# Drivers.net
KiCad netlist of a schematic drawn in Altium Designer
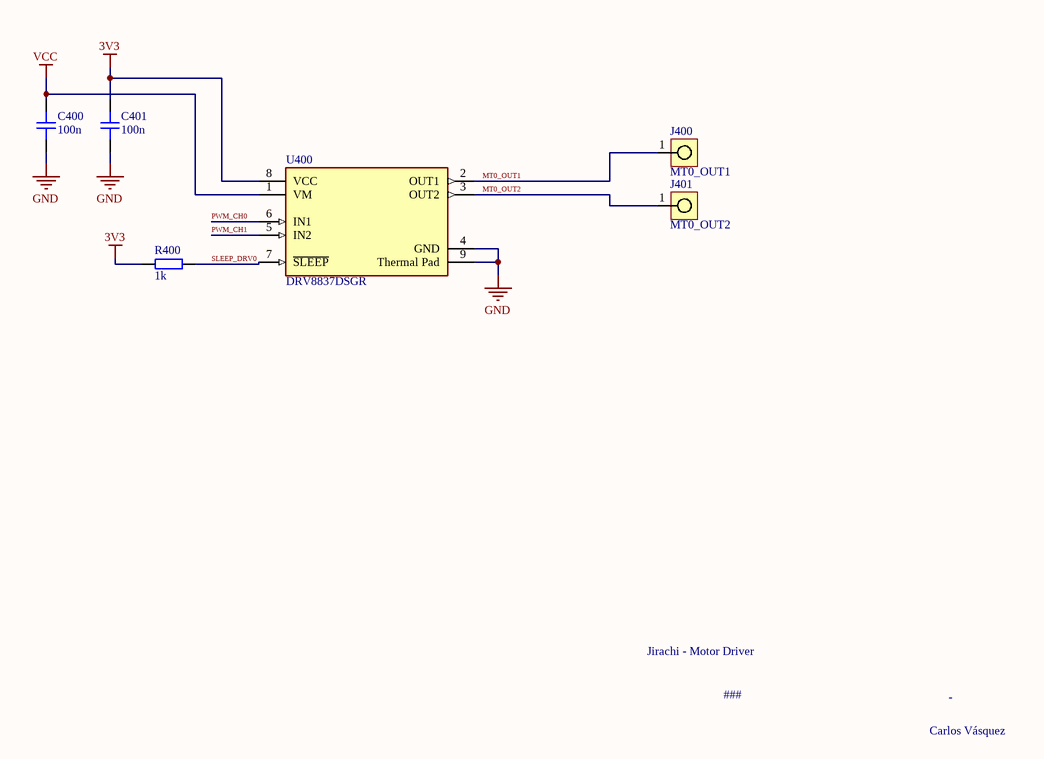
[diagram p0: Drivers.SchDoc]

(export (version "E")
  (design (tool "Eeschema 10.0.6"))
  (components
    (comp (ref "C400")
      (value "100n")
      (footprint "CAP_0402")
      (description "Capacitor SMD 0402")
      (libsource (lib "Schematic-Lib-PhilsLab") (part "CAP_0402"))
    )
    (comp (ref "C401")
      (value "100n")
      (footprint "CAP_0402")
      (description "Capacitor SMD 0402")
      (libsource (lib "Schematic-Lib-PhilsLab") (part "CAP_0402"))
    )
    (comp (ref "J400")
      (value "MT0_OUT1")
      (footprint "SOLDER_PIN_THT_1_5")
      (description "Solder Pin 1.5mm Through-Hole")
      (libsource (lib "Schematic-Lib-PhilsLab") (part "SOLDER_PIN_THT"))
    )
    (comp (ref "J401")
      (value "MT0_OUT2")
      (footprint "SOLDER_PIN_THT_1_5")
      (description "Solder Pin 1.5mm Through-Hole")
      (libsource (lib "Schematic-Lib-PhilsLab") (part "SOLDER_PIN_THT"))
    )
    (comp (ref "R400")
      (value "1k")
      (footprint "RES_0402")
      (description "Resistor SMD 0402")
      (libsource (lib "Schematic-Lib-PhilsLab") (part "RES_0402"))
    )
    (comp (ref "U400")
      (value "DRV8837DSGR")
      (footprint "FP-DSG0008A-MFG")
      (description "IC MOTOR DRIVER PAR 8WSON")
      (fields
        (field (name "MANUFACTURER") "Texas Instruments")
        (field (name "OCTOPART") "https://octopart.com/drv8837dsgr-texas+instruments-23786726")
      )
      (libsource (lib "Altium Content Vault") (part "0edabe62f55b79d65ef7cb8a22a7164"))
    )
  )
  (nets
    (net (code "1") (name "/MT0_OUT1") (class "Default")
      (node (ref "J400") (pin "1") (pinfunction "1_1") (pintype "passive"))
      (node (ref "U400") (pin "2") (pinfunction "OUT1_2") (pintype "output"))
    )
    (net (code "2") (name "/MT0_OUT2") (class "Default")
      (node (ref "J401") (pin "1") (pinfunction "1_1") (pintype "passive"))
      (node (ref "U400") (pin "3") (pinfunction "OUT2_3") (pintype "output"))
    )
    (net (code "3") (name "/PWM_CH0") (class "Default")
      (node (ref "U400") (pin "6") (pinfunction "IN1_6") (pintype "input"))
    )
    (net (code "4") (name "/PWM_CH1") (class "Default")
      (node (ref "U400") (pin "5") (pinfunction "IN2_5") (pintype "input"))
    )
    (net (code "5") (name "/SLEEP_DRV0") (class "Default")
      (node (ref "R400") (pin "1") (pinfunction "1_1") (pintype "passive"))
      (node (ref "U400") (pin "7") (pinfunction "~{SLEEP}_7") (pintype "input"))
    )
    (net (code "6") (name "3V3") (class "Default")
      (node (ref "C401") (pin "2") (pinfunction "2_2") (pintype "passive"))
      (node (ref "R400") (pin "2") (pinfunction "2_2") (pintype "passive"))
      (node (ref "U400") (pin "8") (pinfunction "VCC_8") (pintype "power_in"))
    )
    (net (code "7") (name "GND") (class "Default")
      (node (ref "C400") (pin "1") (pinfunction "1_1") (pintype "passive"))
      (node (ref "C401") (pin "1") (pinfunction "1_1") (pintype "passive"))
      (node (ref "U400") (pin "4") (pinfunction "GND_4") (pintype "power_in"))
      (node (ref "U400") (pin "9") (pinfunction "Thermal_Pad_9") (pintype "power_in"))
    )
    (net (code "8") (name "VCC") (class "Default")
      (node (ref "C400") (pin "2") (pinfunction "2_2") (pintype "passive"))
      (node (ref "U400") (pin "1") (pinfunction "VM_1") (pintype "power_in"))
    )
  )
)
